# Circuit.net
KiCad netlist of a schematic drawn in EAGLE
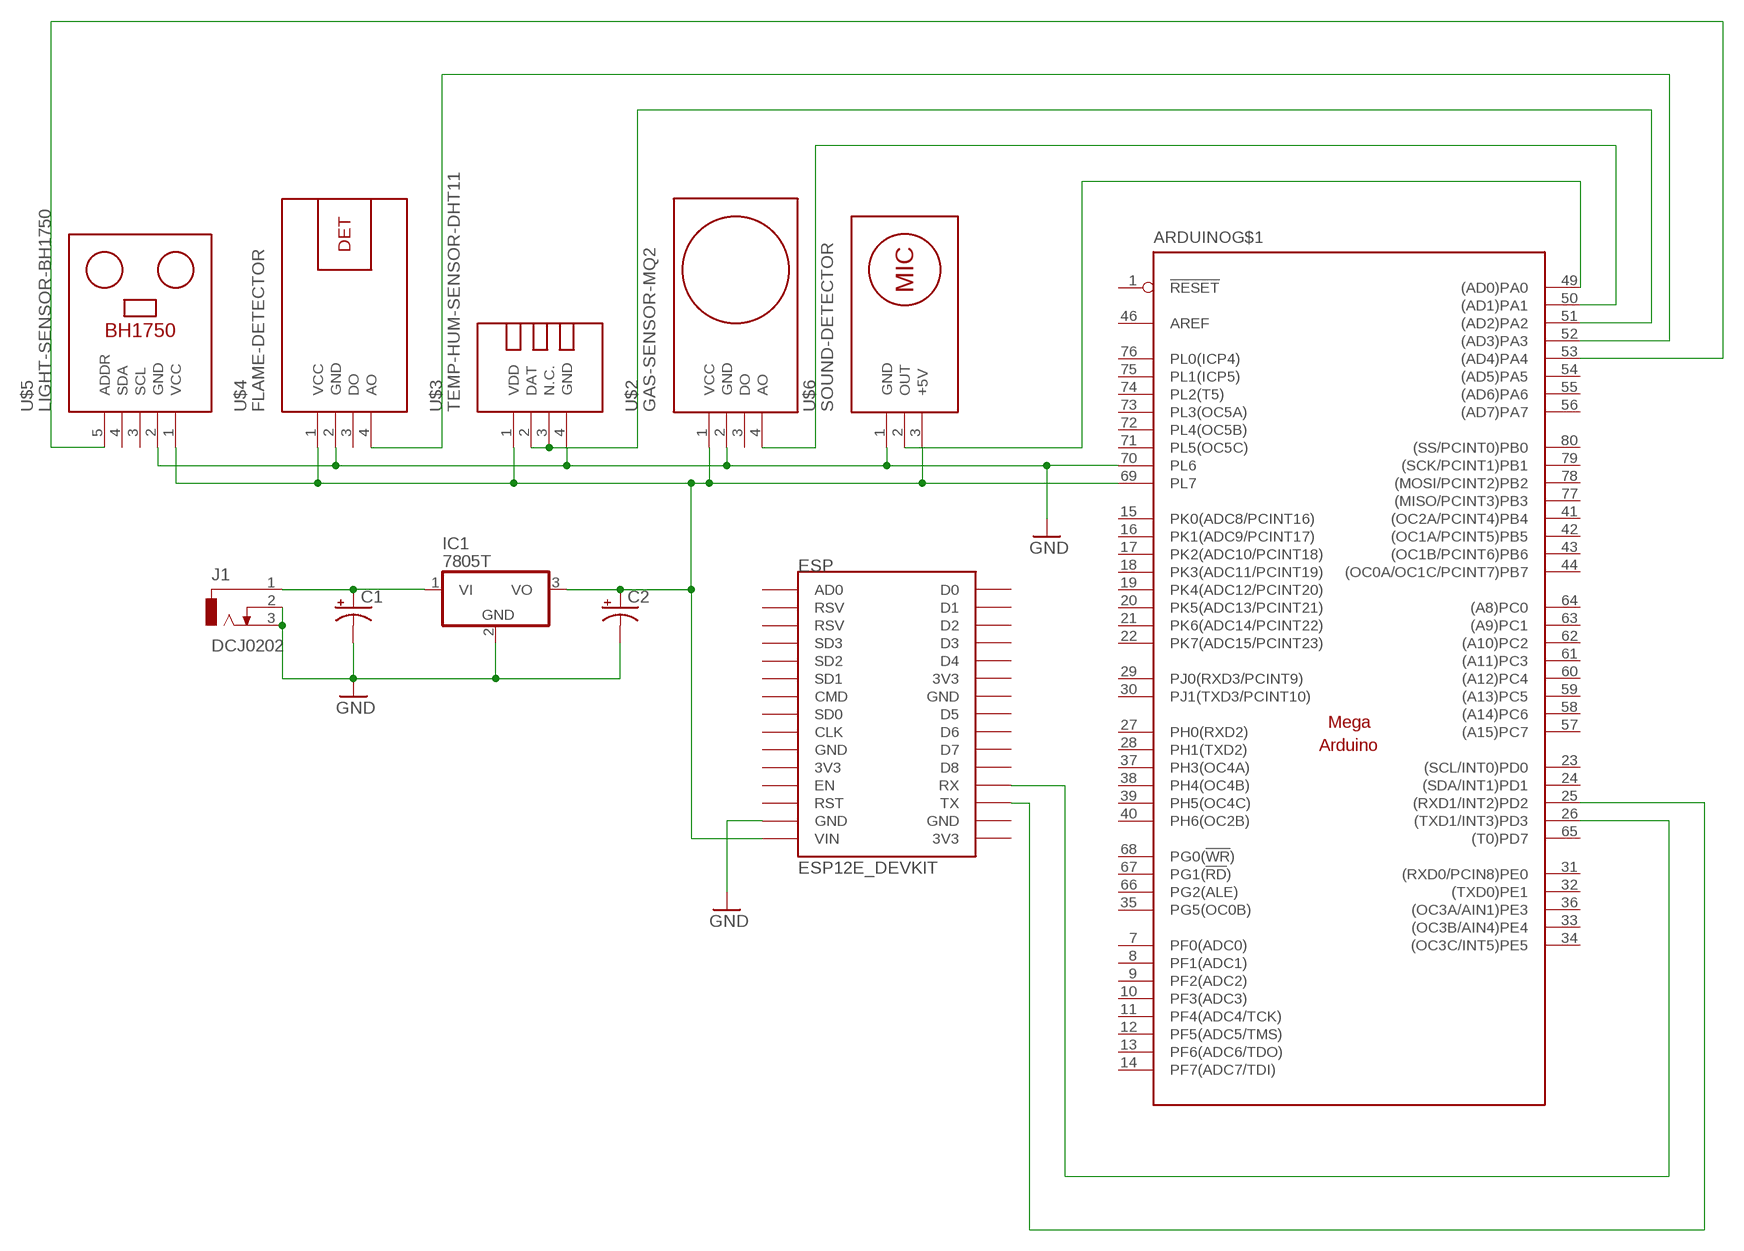
[diagram p0: schematic, sheet 1]

(export (version "E")
  (design (tool "Eeschema 10.0.6"))
  (components
    (comp (ref "ARDUINO")
      (value "MEGAARDUINO_22")
      (footprint "eagle-import:MEGA_ARDUINO_2")
      (libsource (lib "eagle-import") (part "MEGAARDUINO_22"))
    )
    (comp (ref "C1")
      (value "CPOL-USTAP5-45")
      (footprint "eagle-import:TAP5-45")
      (libsource (lib "eagle-import") (part "CPOL-USTAP5-45"))
    )
    (comp (ref "C2")
      (value "CPOL-USTAP5-45")
      (footprint "eagle-import:TAP5-45")
      (libsource (lib "eagle-import") (part "CPOL-USTAP5-45"))
    )
    (comp (ref "ESP")
      (value "ESP12E_DEVKIT")
      (footprint "eagle-import:ESP12E_DEVKIT")
      (libsource (lib "eagle-import") (part "ESP12E_DEVKIT"))
    )
    (comp (ref "IC1")
      (value "7805T")
      (footprint "eagle-import:TO220H")
      (libsource (lib "eagle-import") (part "78T05"))
    )
    (comp (ref "J1")
      (value "DCJ0202")
      (footprint "eagle-import:DCJ0202")
      (libsource (lib "eagle-import") (part "DCJ0202"))
    )
    (comp (ref "U$2")
      (value "GAS-SENSOR-MQ2")
      (footprint "eagle-import:GAS-SENSOR-MQ2")
      (libsource (lib "eagle-import") (part "GAS-SENSOR-MQ2"))
    )
    (comp (ref "U$3")
      (value "TEMP-HUM-SENSOR-DHT11")
      (footprint "eagle-import:TEMP-HUM-SENSOR-DHT11")
      (libsource (lib "eagle-import") (part "TEMP-HUM-SENSOR-DHT11"))
    )
    (comp (ref "U$4")
      (value "FLAME-DETECTOR")
      (footprint "eagle-import:FLAME-DETECTOR")
      (libsource (lib "eagle-import") (part "FLAME-DETECTOR"))
    )
    (comp (ref "U$5")
      (value "LIGHT-SENSOR-BH1750")
      (footprint "eagle-import:LIGHT-SENSOR-BH1750")
      (libsource (lib "eagle-import") (part "LIGHT-SENSOR-BH1750"))
    )
    (comp (ref "U$6")
      (value "SOUND-DETECTOR")
      (footprint "eagle-import:SOUND-DETECTOR")
      (libsource (lib "eagle-import") (part "SOUND-DETECTOR"))
    )
  )
  (nets
    (net (code "1") (name "GND") (class "Default")
      (node (ref "ARDUINO") (pin "70") (pinfunction "PL6_70") (pintype "bidirectional"))
      (node (ref "C1") (pin "-") (pinfunction "-_-") (pintype "passive"))
      (node (ref "C2") (pin "-") (pinfunction "-_-") (pintype "passive"))
      (node (ref "ESP") (pin "GND@1") (pinfunction "GND_GND@1") (pintype "bidirectional"))
      (node (ref "IC1") (pin "2") (pinfunction "GND_2") (pintype "passive"))
      (node (ref "J1") (pin "2") (pinfunction "2_2") (pintype "passive"))
      (node (ref "J1") (pin "3") (pinfunction "3_3") (pintype "passive"))
      (node (ref "U$2") (pin "2") (pinfunction "GND_2") (pintype "power_in"))
      (node (ref "U$3") (pin "4") (pinfunction "GND_4") (pintype "power_in"))
      (node (ref "U$4") (pin "2") (pinfunction "GND_2") (pintype "power_in"))
      (node (ref "U$5") (pin "2") (pinfunction "GND_2") (pintype "power_in"))
      (node (ref "U$6") (pin "1") (pinfunction "GND_1") (pintype "power_in"))
    )
    (net (code "2") (name "Net-(ARDUINOA-(AD0)PA0)") (class "Default")
      (node (ref "ARDUINO") (pin "49") (pinfunction "(AD0)PA0_49") (pintype "bidirectional"))
      (node (ref "U$6") (pin "2") (pinfunction "OUT_2") (pintype "output"))
    )
    (net (code "3") (name "Net-(ARDUINOA-(AD1)PA1)") (class "Default")
      (node (ref "ARDUINO") (pin "50") (pinfunction "(AD1)PA1_50") (pintype "bidirectional"))
      (node (ref "U$2") (pin "4") (pinfunction "AO_4") (pintype "output"))
    )
    (net (code "4") (name "Net-(ARDUINOA-(AD2)PA2)") (class "Default")
      (node (ref "ARDUINO") (pin "51") (pinfunction "(AD2)PA2_51") (pintype "bidirectional"))
      (node (ref "U$3") (pin "2") (pinfunction "DAT_2") (pintype "bidirectional"))
      (node (ref "U$3") (pin "3") (pinfunction "N.C._3") (pintype "passive"))
    )
    (net (code "5") (name "Net-(ARDUINOA-(AD3)PA3)") (class "Default")
      (node (ref "ARDUINO") (pin "52") (pinfunction "(AD3)PA3_52") (pintype "bidirectional"))
      (node (ref "U$4") (pin "4") (pinfunction "AO_4") (pintype "bidirectional"))
    )
    (net (code "6") (name "Net-(ARDUINOA-(AD4)PA4)") (class "Default")
      (node (ref "ARDUINO") (pin "53") (pinfunction "(AD4)PA4_53") (pintype "bidirectional"))
      (node (ref "U$5") (pin "5") (pinfunction "ADDR_5") (pintype "bidirectional"))
    )
    (net (code "7") (name "Net-(ARDUINOA-(RXD1{slash}INT2)PD2)") (class "Default")
      (node (ref "ARDUINO") (pin "25") (pinfunction "(RXD1/INT2)PD2_25") (pintype "bidirectional"))
      (node (ref "ESP") (pin "TX") (pinfunction "TX_TX") (pintype "bidirectional"))
    )
    (net (code "8") (name "Net-(ARDUINOA-(TXD1{slash}INT3)PD3)") (class "Default")
      (node (ref "ARDUINO") (pin "26") (pinfunction "(TXD1/INT3)PD3_26") (pintype "bidirectional"))
      (node (ref "ESP") (pin "RX") (pinfunction "RX_RX") (pintype "bidirectional"))
    )
    (net (code "9") (name "Net-(ARDUINOA-PL7)") (class "Default")
      (node (ref "ARDUINO") (pin "69") (pinfunction "PL7_69") (pintype "bidirectional"))
      (node (ref "C2") (pin "+") (pinfunction "+_+") (pintype "passive"))
      (node (ref "ESP") (pin "VIN") (pinfunction "VIN_VIN") (pintype "bidirectional"))
      (node (ref "IC1") (pin "3") (pinfunction "VO_3") (pintype "passive"))
      (node (ref "U$2") (pin "1") (pinfunction "VCC_1") (pintype "power_in"))
      (node (ref "U$3") (pin "1") (pinfunction "VDD_1") (pintype "power_in"))
      (node (ref "U$4") (pin "1") (pinfunction "VCC_1") (pintype "power_in"))
      (node (ref "U$5") (pin "1") (pinfunction "VCC_1") (pintype "power_in"))
      (node (ref "U$6") (pin "3") (pinfunction "+5V_3") (pintype "power_in"))
    )
    (net (code "10") (name "Net-(IC1-VI)") (class "Default")
      (node (ref "C1") (pin "+") (pinfunction "+_+") (pintype "passive"))
      (node (ref "IC1") (pin "1") (pinfunction "VI_1") (pintype "input"))
      (node (ref "J1") (pin "1") (pinfunction "1_1") (pintype "passive"))
    )
    (net (code "11") (name "unconnected-(ARDUINOA-(A8)PC0-Pad64)") (class "Default")
      (node (ref "ARDUINO") (pin "64") (pinfunction "(A8)PC0_64") (pintype "bidirectional"))
    )
    (net (code "12") (name "unconnected-(ARDUINOA-(A9)PC1-Pad63)") (class "Default")
      (node (ref "ARDUINO") (pin "63") (pinfunction "(A9)PC1_63") (pintype "bidirectional"))
    )
    (net (code "13") (name "unconnected-(ARDUINOA-(A10)PC2-Pad62)") (class "Default")
      (node (ref "ARDUINO") (pin "62") (pinfunction "(A10)PC2_62") (pintype "bidirectional"))
    )
    (net (code "14") (name "unconnected-(ARDUINOA-(A11)PC3-Pad61)") (class "Default")
      (node (ref "ARDUINO") (pin "61") (pinfunction "(A11)PC3_61") (pintype "bidirectional"))
    )
    (net (code "15") (name "unconnected-(ARDUINOA-(A12)PC4-Pad60)") (class "Default")
      (node (ref "ARDUINO") (pin "60") (pinfunction "(A12)PC4_60") (pintype "bidirectional"))
    )
    (net (code "16") (name "unconnected-(ARDUINOA-(A13)PC5-Pad59)") (class "Default")
      (node (ref "ARDUINO") (pin "59") (pinfunction "(A13)PC5_59") (pintype "bidirectional"))
    )
    (net (code "17") (name "unconnected-(ARDUINOA-(A14)PC6-Pad58)") (class "Default")
      (node (ref "ARDUINO") (pin "58") (pinfunction "(A14)PC6_58") (pintype "bidirectional"))
    )
    (net (code "18") (name "unconnected-(ARDUINOA-(A15)PC7-Pad57)") (class "Default")
      (node (ref "ARDUINO") (pin "57") (pinfunction "(A15)PC7_57") (pintype "bidirectional"))
    )
    (net (code "19") (name "unconnected-(ARDUINOA-(AD5)PA5-Pad54)") (class "Default")
      (node (ref "ARDUINO") (pin "54") (pinfunction "(AD5)PA5_54") (pintype "bidirectional"))
    )
    (net (code "20") (name "unconnected-(ARDUINOA-(AD6)PA6-Pad55)") (class "Default")
      (node (ref "ARDUINO") (pin "55") (pinfunction "(AD6)PA6_55") (pintype "bidirectional"))
    )
    (net (code "21") (name "unconnected-(ARDUINOA-(AD7)PA7-Pad56)") (class "Default")
      (node (ref "ARDUINO") (pin "56") (pinfunction "(AD7)PA7_56") (pintype "bidirectional"))
    )
    (net (code "22") (name "unconnected-(ARDUINOA-(MISO{slash}PCINT3)PB3-Pad77)") (class "Default")
      (node (ref "ARDUINO") (pin "77") (pinfunction "(MISO/PCINT3)PB3_77") (pintype "bidirectional"))
    )
    (net (code "23") (name "unconnected-(ARDUINOA-(MOSI{slash}PCINT2)PB2-Pad78)") (class "Default")
      (node (ref "ARDUINO") (pin "78") (pinfunction "(MOSI/PCINT2)PB2_78") (pintype "bidirectional"))
    )
    (net (code "24") (name "unconnected-(ARDUINOA-(OC0A{slash}OC1C{slash}PCINT7)PB7-Pad44)") (class "Default")
      (node (ref "ARDUINO") (pin "44") (pinfunction "(OC0A/OC1C/PCINT7)PB7_44") (pintype "bidirectional"))
    )
    (net (code "25") (name "unconnected-(ARDUINOA-(OC1A{slash}PCINT5)PB5-Pad42)") (class "Default")
      (node (ref "ARDUINO") (pin "42") (pinfunction "(OC1A/PCINT5)PB5_42") (pintype "bidirectional"))
    )
    (net (code "26") (name "unconnected-(ARDUINOA-(OC1B{slash}PCINT6)PB6-Pad43)") (class "Default")
      (node (ref "ARDUINO") (pin "43") (pinfunction "(OC1B/PCINT6)PB6_43") (pintype "bidirectional"))
    )
    (net (code "27") (name "unconnected-(ARDUINOA-(OC2A{slash}PCINT4)PB4-Pad41)") (class "Default")
      (node (ref "ARDUINO") (pin "41") (pinfunction "(OC2A/PCINT4)PB4_41") (pintype "bidirectional"))
    )
    (net (code "28") (name "unconnected-(ARDUINOA-(OC3A{slash}AIN1)PE3-Pad36)") (class "Default")
      (node (ref "ARDUINO") (pin "36") (pinfunction "(OC3A/AIN1)PE3_36") (pintype "bidirectional"))
    )
    (net (code "29") (name "unconnected-(ARDUINOA-(OC3B{slash}AIN4)PE4-Pad33)") (class "Default")
      (node (ref "ARDUINO") (pin "33") (pinfunction "(OC3B/AIN4)PE4_33") (pintype "bidirectional"))
    )
    (net (code "30") (name "unconnected-(ARDUINOA-(OC3C{slash}INT5)PE5-Pad34)") (class "Default")
      (node (ref "ARDUINO") (pin "34") (pinfunction "(OC3C/INT5)PE5_34") (pintype "bidirectional"))
    )
    (net (code "31") (name "unconnected-(ARDUINOA-(RXD0{slash}PCIN8)PE0-Pad31)") (class "Default")
      (node (ref "ARDUINO") (pin "31") (pinfunction "(RXD0/PCIN8)PE0_31") (pintype "bidirectional"))
    )
    (net (code "32") (name "unconnected-(ARDUINOA-(SCK{slash}PCINT1)PB1-Pad79)") (class "Default")
      (node (ref "ARDUINO") (pin "79") (pinfunction "(SCK/PCINT1)PB1_79") (pintype "bidirectional"))
    )
    (net (code "33") (name "unconnected-(ARDUINOA-(SCL{slash}INT0)PD0-Pad23)") (class "Default")
      (node (ref "ARDUINO") (pin "23") (pinfunction "(SCL/INT0)PD0_23") (pintype "bidirectional"))
    )
    (net (code "34") (name "unconnected-(ARDUINOA-(SDA{slash}INT1)PD1-Pad24)") (class "Default")
      (node (ref "ARDUINO") (pin "24") (pinfunction "(SDA/INT1)PD1_24") (pintype "bidirectional"))
    )
    (net (code "35") (name "unconnected-(ARDUINOA-(SS{slash}PCINT0)PB0-Pad80)") (class "Default")
      (node (ref "ARDUINO") (pin "80") (pinfunction "(SS/PCINT0)PB0_80") (pintype "bidirectional"))
    )
    (net (code "36") (name "unconnected-(ARDUINOA-(T0)PD7-Pad65)") (class "Default")
      (node (ref "ARDUINO") (pin "65") (pinfunction "(T0)PD7_65") (pintype "bidirectional"))
    )
    (net (code "37") (name "unconnected-(ARDUINOA-(TXD0)PE1-Pad32)") (class "Default")
      (node (ref "ARDUINO") (pin "32") (pinfunction "(TXD0)PE1_32") (pintype "bidirectional"))
    )
    (net (code "38") (name "unconnected-(ARDUINOA-AREF-Pad46)") (class "Default")
      (node (ref "ARDUINO") (pin "46") (pinfunction "AREF_46") (pintype "bidirectional"))
    )
    (net (code "39") (name "unconnected-(ARDUINOA-PF0(ADC0)-Pad7)") (class "Default")
      (node (ref "ARDUINO") (pin "7") (pinfunction "PF0(ADC0)_7") (pintype "bidirectional"))
    )
    (net (code "40") (name "unconnected-(ARDUINOA-PF1(ADC1)-Pad8)") (class "Default")
      (node (ref "ARDUINO") (pin "8") (pinfunction "PF1(ADC1)_8") (pintype "bidirectional"))
    )
    (net (code "41") (name "unconnected-(ARDUINOA-PF2(ADC2)-Pad9)") (class "Default")
      (node (ref "ARDUINO") (pin "9") (pinfunction "PF2(ADC2)_9") (pintype "bidirectional"))
    )
    (net (code "42") (name "unconnected-(ARDUINOA-PF3(ADC3)-Pad10)") (class "Default")
      (node (ref "ARDUINO") (pin "10") (pinfunction "PF3(ADC3)_10") (pintype "bidirectional"))
    )
    (net (code "43") (name "unconnected-(ARDUINOA-PF4(ADC4{slash}TCK)-Pad11)") (class "Default")
      (node (ref "ARDUINO") (pin "11") (pinfunction "PF4(ADC4/TCK)_11") (pintype "bidirectional"))
    )
    (net (code "44") (name "unconnected-(ARDUINOA-PF5(ADC5{slash}TMS)-Pad12)") (class "Default")
      (node (ref "ARDUINO") (pin "12") (pinfunction "PF5(ADC5/TMS)_12") (pintype "bidirectional"))
    )
    (net (code "45") (name "unconnected-(ARDUINOA-PF6(ADC6{slash}TDO)-Pad13)") (class "Default")
      (node (ref "ARDUINO") (pin "13") (pinfunction "PF6(ADC6/TDO)_13") (pintype "bidirectional"))
    )
    (net (code "46") (name "unconnected-(ARDUINOA-PF7(ADC7{slash}TDI)-Pad14)") (class "Default")
      (node (ref "ARDUINO") (pin "14") (pinfunction "PF7(ADC7/TDI)_14") (pintype "bidirectional"))
    )
    (net (code "47") (name "unconnected-(ARDUINOA-PG0(~{WR})-Pad68)") (class "Default")
      (node (ref "ARDUINO") (pin "68") (pinfunction "PG0(~{WR})_68") (pintype "bidirectional"))
    )
    (net (code "48") (name "unconnected-(ARDUINOA-PG1(~{RD})-Pad67)") (class "Default")
      (node (ref "ARDUINO") (pin "67") (pinfunction "PG1(~{RD})_67") (pintype "bidirectional"))
    )
    (net (code "49") (name "unconnected-(ARDUINOA-PG2(ALE)-Pad66)") (class "Default")
      (node (ref "ARDUINO") (pin "66") (pinfunction "PG2(ALE)_66") (pintype "bidirectional"))
    )
    (net (code "50") (name "unconnected-(ARDUINOA-PG5(OC0B)-Pad35)") (class "Default")
      (node (ref "ARDUINO") (pin "35") (pinfunction "PG5(OC0B)_35") (pintype "bidirectional"))
    )
    (net (code "51") (name "unconnected-(ARDUINOA-PH0(RXD2)-Pad27)") (class "Default")
      (node (ref "ARDUINO") (pin "27") (pinfunction "PH0(RXD2)_27") (pintype "bidirectional"))
    )
    (net (code "52") (name "unconnected-(ARDUINOA-PH1(TXD2)-Pad28)") (class "Default")
      (node (ref "ARDUINO") (pin "28") (pinfunction "PH1(TXD2)_28") (pintype "bidirectional"))
    )
    (net (code "53") (name "unconnected-(ARDUINOA-PH3(OC4A)-Pad37)") (class "Default")
      (node (ref "ARDUINO") (pin "37") (pinfunction "PH3(OC4A)_37") (pintype "bidirectional"))
    )
    (net (code "54") (name "unconnected-(ARDUINOA-PH4(OC4B)-Pad38)") (class "Default")
      (node (ref "ARDUINO") (pin "38") (pinfunction "PH4(OC4B)_38") (pintype "bidirectional"))
    )
    (net (code "55") (name "unconnected-(ARDUINOA-PH5(OC4C)-Pad39)") (class "Default")
      (node (ref "ARDUINO") (pin "39") (pinfunction "PH5(OC4C)_39") (pintype "bidirectional"))
    )
    (net (code "56") (name "unconnected-(ARDUINOA-PH6(OC2B)-Pad40)") (class "Default")
      (node (ref "ARDUINO") (pin "40") (pinfunction "PH6(OC2B)_40") (pintype "bidirectional"))
    )
    (net (code "57") (name "unconnected-(ARDUINOA-PJ0(RXD3{slash}PCINT9)-Pad29)") (class "Default")
      (node (ref "ARDUINO") (pin "29") (pinfunction "PJ0(RXD3/PCINT9)_29") (pintype "bidirectional"))
    )
    (net (code "58") (name "unconnected-(ARDUINOA-PJ1(TXD3{slash}PCINT10)-Pad30)") (class "Default")
      (node (ref "ARDUINO") (pin "30") (pinfunction "PJ1(TXD3/PCINT10)_30") (pintype "bidirectional"))
    )
    (net (code "59") (name "unconnected-(ARDUINOA-PK0(ADC8{slash}PCINT16)-Pad15)") (class "Default")
      (node (ref "ARDUINO") (pin "15") (pinfunction "PK0(ADC8/PCINT16)_15") (pintype "bidirectional"))
    )
    (net (code "60") (name "unconnected-(ARDUINOA-PK1(ADC9{slash}PCINT17)-Pad16)") (class "Default")
      (node (ref "ARDUINO") (pin "16") (pinfunction "PK1(ADC9/PCINT17)_16") (pintype "bidirectional"))
    )
    (net (code "61") (name "unconnected-(ARDUINOA-PK2(ADC10{slash}PCINT18)-Pad17)") (class "Default")
      (node (ref "ARDUINO") (pin "17") (pinfunction "PK2(ADC10/PCINT18)_17") (pintype "bidirectional"))
    )
    (net (code "62") (name "unconnected-(ARDUINOA-PK3(ADC11{slash}PCINT19)-Pad18)") (class "Default")
      (node (ref "ARDUINO") (pin "18") (pinfunction "PK3(ADC11/PCINT19)_18") (pintype "bidirectional"))
    )
    (net (code "63") (name "unconnected-(ARDUINOA-PK4(ADC12{slash}PCINT20)-Pad19)") (class "Default")
      (node (ref "ARDUINO") (pin "19") (pinfunction "PK4(ADC12/PCINT20)_19") (pintype "bidirectional"))
    )
    (net (code "64") (name "unconnected-(ARDUINOA-PK5(ADC13{slash}PCINT21)-Pad20)") (class "Default")
      (node (ref "ARDUINO") (pin "20") (pinfunction "PK5(ADC13/PCINT21)_20") (pintype "bidirectional"))
    )
    (net (code "65") (name "unconnected-(ARDUINOA-PK6(ADC14{slash}PCINT22)-Pad21)") (class "Default")
      (node (ref "ARDUINO") (pin "21") (pinfunction "PK6(ADC14/PCINT22)_21") (pintype "bidirectional"))
    )
    (net (code "66") (name "unconnected-(ARDUINOA-PK7(ADC15{slash}PCINT23)-Pad22)") (class "Default")
      (node (ref "ARDUINO") (pin "22") (pinfunction "PK7(ADC15/PCINT23)_22") (pintype "bidirectional"))
    )
    (net (code "67") (name "unconnected-(ARDUINOA-PL0(ICP4)-Pad76)") (class "Default")
      (node (ref "ARDUINO") (pin "76") (pinfunction "PL0(ICP4)_76") (pintype "bidirectional"))
    )
    (net (code "68") (name "unconnected-(ARDUINOA-PL1(ICP5)-Pad75)") (class "Default")
      (node (ref "ARDUINO") (pin "75") (pinfunction "PL1(ICP5)_75") (pintype "bidirectional"))
    )
    (net (code "69") (name "unconnected-(ARDUINOA-PL2(T5)-Pad74)") (class "Default")
      (node (ref "ARDUINO") (pin "74") (pinfunction "PL2(T5)_74") (pintype "bidirectional"))
    )
    (net (code "70") (name "unconnected-(ARDUINOA-PL3(OC5A)-Pad73)") (class "Default")
      (node (ref "ARDUINO") (pin "73") (pinfunction "PL3(OC5A)_73") (pintype "bidirectional"))
    )
    (net (code "71") (name "unconnected-(ARDUINOA-PL4(OC5B)-Pad72)") (class "Default")
      (node (ref "ARDUINO") (pin "72") (pinfunction "PL4(OC5B)_72") (pintype "bidirectional"))
    )
    (net (code "72") (name "unconnected-(ARDUINOA-PL5(OC5C)-Pad71)") (class "Default")
      (node (ref "ARDUINO") (pin "71") (pinfunction "PL5(OC5C)_71") (pintype "bidirectional"))
    )
    (net (code "73") (name "unconnected-(ARDUINOA-~{RESET}-Pad1)") (class "Default")
      (node (ref "ARDUINO") (pin "1") (pinfunction "~{RESET}_1") (pintype "bidirectional"))
    )
    (net (code "74") (name "unconnected-(ESP-3V3-Pad3V3@0)") (class "Default")
      (node (ref "ESP") (pin "3V3@0") (pinfunction "3V3_3V3@0") (pintype "bidirectional"))
    )
    (net (code "75") (name "unconnected-(ESP-3V3-Pad3V3@1)") (class "Default")
      (node (ref "ESP") (pin "3V3@1") (pinfunction "3V3_3V3@1") (pintype "bidirectional"))
    )
    (net (code "76") (name "unconnected-(ESP-3V3-Pad3V3@2)") (class "Default")
      (node (ref "ESP") (pin "3V3@2") (pinfunction "3V3_3V3@2") (pintype "bidirectional"))
    )
    (net (code "77") (name "unconnected-(ESP-GND-PadGND@0)") (class "Default")
      (node (ref "ESP") (pin "GND@0") (pinfunction "GND_GND@0") (pintype "bidirectional"))
    )
    (net (code "78") (name "unconnected-(ESP-GND-PadGND@2)") (class "Default")
      (node (ref "ESP") (pin "GND@2") (pinfunction "GND_GND@2") (pintype "bidirectional"))
    )
    (net (code "79") (name "unconnected-(ESP-GND-PadGND@3)") (class "Default")
      (node (ref "ESP") (pin "GND@3") (pinfunction "GND_GND@3") (pintype "bidirectional"))
    )
    (net (code "80") (name "unconnected-(ESP-PadAD0)") (class "Default")
      (node (ref "ESP") (pin "AD0") (pinfunction "AD0_AD0") (pintype "bidirectional"))
    )
    (net (code "81") (name "unconnected-(ESP-PadCLK)") (class "Default")
      (node (ref "ESP") (pin "CLK") (pinfunction "CLK_CLK") (pintype "bidirectional"))
    )
    (net (code "82") (name "unconnected-(ESP-PadCMD)") (class "Default")
      (node (ref "ESP") (pin "CMD") (pinfunction "CMD_CMD") (pintype "bidirectional"))
    )
    (net (code "83") (name "unconnected-(ESP-PadD0)") (class "Default")
      (node (ref "ESP") (pin "D0") (pinfunction "D0_D0") (pintype "bidirectional"))
    )
    (net (code "84") (name "unconnected-(ESP-PadD1)") (class "Default")
      (node (ref "ESP") (pin "D1") (pinfunction "D1_D1") (pintype "bidirectional"))
    )
    (net (code "85") (name "unconnected-(ESP-PadD2)") (class "Default")
      (node (ref "ESP") (pin "D2") (pinfunction "D2_D2") (pintype "bidirectional"))
    )
    (net (code "86") (name "unconnected-(ESP-PadD3)") (class "Default")
      (node (ref "ESP") (pin "D3") (pinfunction "D3_D3") (pintype "bidirectional"))
    )
    (net (code "87") (name "unconnected-(ESP-PadD4)") (class "Default")
      (node (ref "ESP") (pin "D4") (pinfunction "D4_D4") (pintype "bidirectional"))
    )
    (net (code "88") (name "unconnected-(ESP-PadD5)") (class "Default")
      (node (ref "ESP") (pin "D5") (pinfunction "D5_D5") (pintype "bidirectional"))
    )
    (net (code "89") (name "unconnected-(ESP-PadD6)") (class "Default")
      (node (ref "ESP") (pin "D6") (pinfunction "D6_D6") (pintype "bidirectional"))
    )
    (net (code "90") (name "unconnected-(ESP-PadD7)") (class "Default")
      (node (ref "ESP") (pin "D7") (pinfunction "D7_D7") (pintype "bidirectional"))
    )
    (net (code "91") (name "unconnected-(ESP-PadD8)") (class "Default")
      (node (ref "ESP") (pin "D8") (pinfunction "D8_D8") (pintype "bidirectional"))
    )
    (net (code "92") (name "unconnected-(ESP-PadEN)") (class "Default")
      (node (ref "ESP") (pin "EN") (pinfunction "EN_EN") (pintype "bidirectional"))
    )
    (net (code "93") (name "unconnected-(ESP-PadRST)") (class "Default")
      (node (ref "ESP") (pin "RST") (pinfunction "RST_RST") (pintype "bidirectional"))
    )
    (net (code "94") (name "unconnected-(ESP-PadSD0)") (class "Default")
      (node (ref "ESP") (pin "SD0") (pinfunction "SD0_SD0") (pintype "bidirectional"))
    )
    (net (code "95") (name "unconnected-(ESP-PadSD1)") (class "Default")
      (node (ref "ESP") (pin "SD1") (pinfunction "SD1_SD1") (pintype "bidirectional"))
    )
    (net (code "96") (name "unconnected-(ESP-PadSD2)") (class "Default")
      (node (ref "ESP") (pin "SD2") (pinfunction "SD2_SD2") (pintype "bidirectional"))
    )
    (net (code "97") (name "unconnected-(ESP-PadSD3)") (class "Default")
      (node (ref "ESP") (pin "SD3") (pinfunction "SD3_SD3") (pintype "bidirectional"))
    )
    (net (code "98") (name "unconnected-(ESP-RSV-PadRSV@0)") (class "Default")
      (node (ref "ESP") (pin "RSV@0") (pinfunction "RSV_RSV@0") (pintype "bidirectional"))
    )
    (net (code "99") (name "unconnected-(ESP-RSV-PadRSV@1)") (class "Default")
      (node (ref "ESP") (pin "RSV@1") (pinfunction "RSV_RSV@1") (pintype "bidirectional"))
    )
    (net (code "100") (name "unconnected-(U$2-DO-Pad3)") (class "Default")
      (node (ref "U$2") (pin "3") (pinfunction "DO_3") (pintype "output"))
    )
    (net (code "101") (name "unconnected-(U$4-DO-Pad3)") (class "Default")
      (node (ref "U$4") (pin "3") (pinfunction "DO_3") (pintype "bidirectional"))
    )
    (net (code "102") (name "unconnected-(U$5-SCL-Pad3)") (class "Default")
      (node (ref "U$5") (pin "3") (pinfunction "SCL_3") (pintype "bidirectional"))
    )
    (net (code "103") (name "unconnected-(U$5-SDA-Pad4)") (class "Default")
      (node (ref "U$5") (pin "4") (pinfunction "SDA_4") (pintype "bidirectional"))
    )
  )
)
